# APA106_layout_test.net
KiCad netlist of a schematic drawn in EAGLE
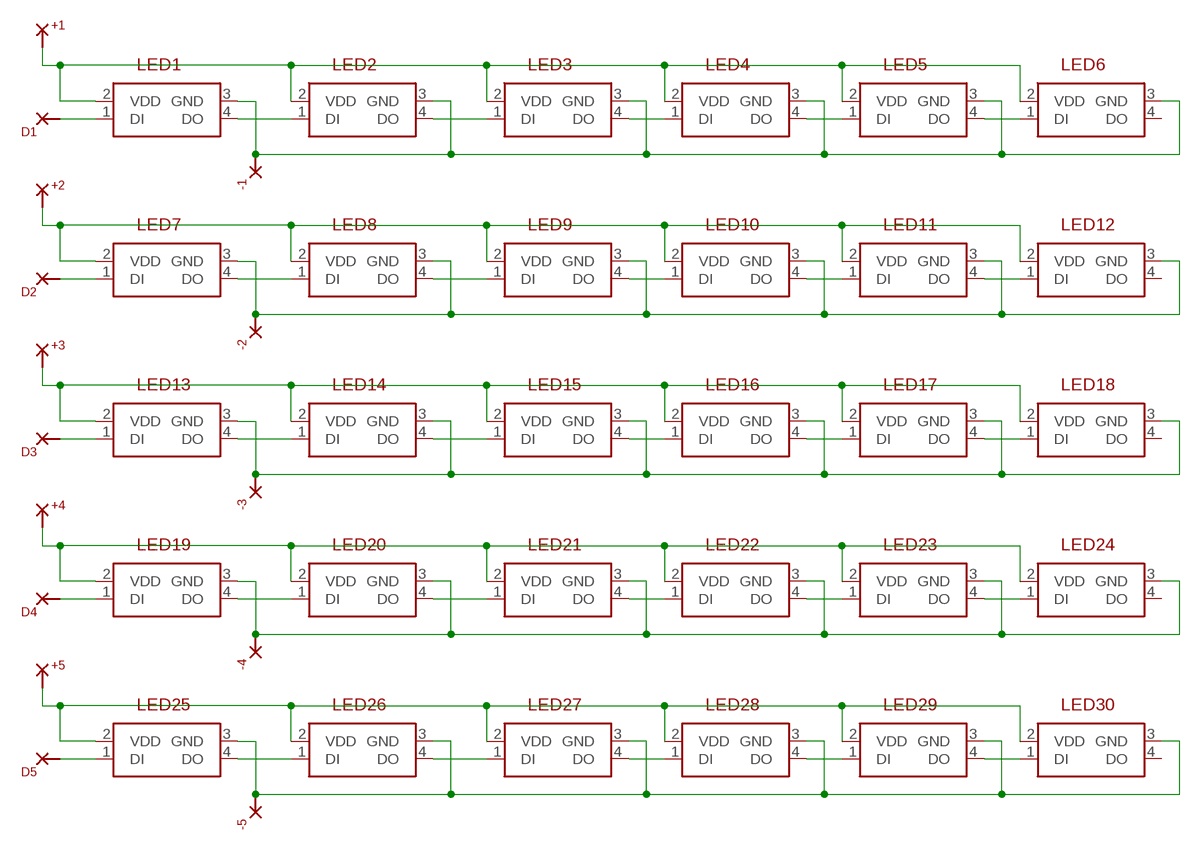
[diagram p0: schematic, sheet 1]

(export (version "E")
  (design (tool "Eeschema 10.0.6"))
  (components
    (comp (ref "+1")
      (value "WIRE-TEST-LOOP")
      (footprint "eagle-import:WIRE-TEST-LOOP")
      (libsource (lib "eagle-import") (part "WIRE-TEST-LOOP"))
    )
    (comp (ref "+2")
      (value "WIRE-TEST-LOOP")
      (footprint "eagle-import:WIRE-TEST-LOOP")
      (libsource (lib "eagle-import") (part "WIRE-TEST-LOOP"))
    )
    (comp (ref "+3")
      (value "WIRE-TEST-LOOP")
      (footprint "eagle-import:WIRE-TEST-LOOP")
      (libsource (lib "eagle-import") (part "WIRE-TEST-LOOP"))
    )
    (comp (ref "+4")
      (value "WIRE-TEST-LOOP")
      (footprint "eagle-import:WIRE-TEST-LOOP")
      (libsource (lib "eagle-import") (part "WIRE-TEST-LOOP"))
    )
    (comp (ref "+5")
      (value "WIRE-TEST-LOOP")
      (footprint "eagle-import:WIRE-TEST-LOOP")
      (libsource (lib "eagle-import") (part "WIRE-TEST-LOOP"))
    )
    (comp (ref "-1")
      (value "WIRE-TEST-LOOP")
      (footprint "eagle-import:WIRE-TEST-LOOP")
      (libsource (lib "eagle-import") (part "WIRE-TEST-LOOP"))
    )
    (comp (ref "-2")
      (value "WIRE-TEST-LOOP")
      (footprint "eagle-import:WIRE-TEST-LOOP")
      (libsource (lib "eagle-import") (part "WIRE-TEST-LOOP"))
    )
    (comp (ref "-3")
      (value "WIRE-TEST-LOOP")
      (footprint "eagle-import:WIRE-TEST-LOOP")
      (libsource (lib "eagle-import") (part "WIRE-TEST-LOOP"))
    )
    (comp (ref "-4")
      (value "WIRE-TEST-LOOP")
      (footprint "eagle-import:WIRE-TEST-LOOP")
      (libsource (lib "eagle-import") (part "WIRE-TEST-LOOP"))
    )
    (comp (ref "-5")
      (value "WIRE-TEST-LOOP")
      (footprint "eagle-import:WIRE-TEST-LOOP")
      (libsource (lib "eagle-import") (part "WIRE-TEST-LOOP"))
    )
    (comp (ref "D1")
      (value "WIRE-TEST-LOOP")
      (footprint "eagle-import:WIRE-TEST-LOOP")
      (libsource (lib "eagle-import") (part "WIRE-TEST-LOOP"))
    )
    (comp (ref "D2")
      (value "WIRE-TEST-LOOP")
      (footprint "eagle-import:WIRE-TEST-LOOP")
      (libsource (lib "eagle-import") (part "WIRE-TEST-LOOP"))
    )
    (comp (ref "D3")
      (value "WIRE-TEST-LOOP")
      (footprint "eagle-import:WIRE-TEST-LOOP")
      (libsource (lib "eagle-import") (part "WIRE-TEST-LOOP"))
    )
    (comp (ref "D4")
      (value "WIRE-TEST-LOOP")
      (footprint "eagle-import:WIRE-TEST-LOOP")
      (libsource (lib "eagle-import") (part "WIRE-TEST-LOOP"))
    )
    (comp (ref "D5")
      (value "WIRE-TEST-LOOP")
      (footprint "eagle-import:WIRE-TEST-LOOP")
      (libsource (lib "eagle-import") (part "WIRE-TEST-LOOP"))
    )
    (comp (ref "LED1")
      (value "LED-APA106HOLE-OFFSET-SPREAD")
      (footprint "eagle-import:LED-5MM-4PIN-HOLE-OFFSET-SPREAD")
      (libsource (lib "eagle-import") (part "LED-APA106HOLE-OFFSET-SPREAD"))
    )
    (comp (ref "LED2")
      (value "LED-APA106HOLE-OFFSET-SPREAD")
      (footprint "eagle-import:LED-5MM-4PIN-HOLE-OFFSET-SPREAD")
      (libsource (lib "eagle-import") (part "LED-APA106HOLE-OFFSET-SPREAD"))
    )
    (comp (ref "LED3")
      (value "LED-APA106HOLE-OFFSET-SPREAD")
      (footprint "eagle-import:LED-5MM-4PIN-HOLE-OFFSET-SPREAD")
      (libsource (lib "eagle-import") (part "LED-APA106HOLE-OFFSET-SPREAD"))
    )
    (comp (ref "LED4")
      (value "LED-APA106HOLE-OFFSET-SPREAD")
      (footprint "eagle-import:LED-5MM-4PIN-HOLE-OFFSET-SPREAD")
      (libsource (lib "eagle-import") (part "LED-APA106HOLE-OFFSET-SPREAD"))
    )
    (comp (ref "LED5")
      (value "LED-APA106HOLE-OFFSET-SPREAD")
      (footprint "eagle-import:LED-5MM-4PIN-HOLE-OFFSET-SPREAD")
      (libsource (lib "eagle-import") (part "LED-APA106HOLE-OFFSET-SPREAD"))
    )
    (comp (ref "LED6")
      (value "LED-APA106HOLE-OFFSET-SPREAD")
      (footprint "eagle-import:LED-5MM-4PIN-HOLE-OFFSET-SPREAD")
      (libsource (lib "eagle-import") (part "LED-APA106HOLE-OFFSET-SPREAD"))
    )
    (comp (ref "LED7")
      (value "LED-APA106SPREAD")
      (footprint "eagle-import:LED-5MM-4PIN-SPREAD")
      (libsource (lib "eagle-import") (part "LED-APA106SPREAD"))
    )
    (comp (ref "LED8")
      (value "LED-APA106SPREAD")
      (footprint "eagle-import:LED-5MM-4PIN-SPREAD")
      (libsource (lib "eagle-import") (part "LED-APA106SPREAD"))
    )
    (comp (ref "LED9")
      (value "LED-APA106SPREAD")
      (footprint "eagle-import:LED-5MM-4PIN-SPREAD")
      (libsource (lib "eagle-import") (part "LED-APA106SPREAD"))
    )
    (comp (ref "LED10")
      (value "LED-APA106SPREAD")
      (footprint "eagle-import:LED-5MM-4PIN-SPREAD")
      (libsource (lib "eagle-import") (part "LED-APA106SPREAD"))
    )
    (comp (ref "LED11")
      (value "LED-APA106SPREAD")
      (footprint "eagle-import:LED-5MM-4PIN-SPREAD")
      (libsource (lib "eagle-import") (part "LED-APA106SPREAD"))
    )
    (comp (ref "LED12")
      (value "LED-APA106SPREAD")
      (footprint "eagle-import:LED-5MM-4PIN-SPREAD")
      (libsource (lib "eagle-import") (part "LED-APA106SPREAD"))
    )
    (comp (ref "LED13")
      (value "LED-APA106OFFSET")
      (footprint "eagle-import:LED-5MM-4PIN-OFFSET")
      (libsource (lib "eagle-import") (part "LED-APA106OFFSET"))
    )
    (comp (ref "LED14")
      (value "LED-APA106OFFSET")
      (footprint "eagle-import:LED-5MM-4PIN-OFFSET")
      (libsource (lib "eagle-import") (part "LED-APA106OFFSET"))
    )
    (comp (ref "LED15")
      (value "LED-APA106OFFSET")
      (footprint "eagle-import:LED-5MM-4PIN-OFFSET")
      (libsource (lib "eagle-import") (part "LED-APA106OFFSET"))
    )
    (comp (ref "LED16")
      (value "LED-APA106OFFSET")
      (footprint "eagle-import:LED-5MM-4PIN-OFFSET")
      (libsource (lib "eagle-import") (part "LED-APA106OFFSET"))
    )
    (comp (ref "LED17")
      (value "LED-APA106OFFSET")
      (footprint "eagle-import:LED-5MM-4PIN-OFFSET")
      (libsource (lib "eagle-import") (part "LED-APA106OFFSET"))
    )
    (comp (ref "LED18")
      (value "LED-APA106OFFSET")
      (footprint "eagle-import:LED-5MM-4PIN-OFFSET")
      (libsource (lib "eagle-import") (part "LED-APA106OFFSET"))
    )
    (comp (ref "LED19")
      (value "LED-APA106SPREAD-OFFSET")
      (footprint "eagle-import:LED-5MM-4PIN-SPREAD-OFFSET")
      (libsource (lib "eagle-import") (part "LED-APA106SPREAD-OFFSET"))
    )
    (comp (ref "LED20")
      (value "LED-APA106SPREAD-OFFSET")
      (footprint "eagle-import:LED-5MM-4PIN-SPREAD-OFFSET")
      (libsource (lib "eagle-import") (part "LED-APA106SPREAD-OFFSET"))
    )
    (comp (ref "LED21")
      (value "LED-APA106SPREAD-OFFSET")
      (footprint "eagle-import:LED-5MM-4PIN-SPREAD-OFFSET")
      (libsource (lib "eagle-import") (part "LED-APA106SPREAD-OFFSET"))
    )
    (comp (ref "LED22")
      (value "LED-APA106SPREAD-OFFSET")
      (footprint "eagle-import:LED-5MM-4PIN-SPREAD-OFFSET")
      (libsource (lib "eagle-import") (part "LED-APA106SPREAD-OFFSET"))
    )
    (comp (ref "LED23")
      (value "LED-APA106SPREAD-OFFSET")
      (footprint "eagle-import:LED-5MM-4PIN-SPREAD-OFFSET")
      (libsource (lib "eagle-import") (part "LED-APA106SPREAD-OFFSET"))
    )
    (comp (ref "LED24")
      (value "LED-APA106SPREAD-OFFSET")
      (footprint "eagle-import:LED-5MM-4PIN-SPREAD-OFFSET")
      (libsource (lib "eagle-import") (part "LED-APA106SPREAD-OFFSET"))
    )
    (comp (ref "LED25")
      (value "LED-APA106HOLE-OFFSET")
      (footprint "eagle-import:LED-5MM-4PIN-HOLE-OFFSET")
      (libsource (lib "eagle-import") (part "LED-APA106HOLE-OFFSET"))
    )
    (comp (ref "LED26")
      (value "LED-APA106HOLE-OFFSET")
      (footprint "eagle-import:LED-5MM-4PIN-HOLE-OFFSET")
      (libsource (lib "eagle-import") (part "LED-APA106HOLE-OFFSET"))
    )
    (comp (ref "LED27")
      (value "LED-APA106HOLE-OFFSET")
      (footprint "eagle-import:LED-5MM-4PIN-HOLE-OFFSET")
      (libsource (lib "eagle-import") (part "LED-APA106HOLE-OFFSET"))
    )
    (comp (ref "LED28")
      (value "LED-APA106HOLE-OFFSET")
      (footprint "eagle-import:LED-5MM-4PIN-HOLE-OFFSET")
      (libsource (lib "eagle-import") (part "LED-APA106HOLE-OFFSET"))
    )
    (comp (ref "LED29")
      (value "LED-APA106HOLE-OFFSET")
      (footprint "eagle-import:LED-5MM-4PIN-HOLE-OFFSET")
      (libsource (lib "eagle-import") (part "LED-APA106HOLE-OFFSET"))
    )
    (comp (ref "LED30")
      (value "LED-APA106HOLE-OFFSET")
      (footprint "eagle-import:LED-5MM-4PIN-HOLE-OFFSET")
      (libsource (lib "eagle-import") (part "LED-APA106HOLE-OFFSET"))
    )
  )
  (nets
    (net (code "1") (name "Net-(LED1-DI)") (class "Default")
      (node (ref "D1") (pin "HOLE1") (pinfunction "1_HOLE1") (pintype "bidirectional"))
      (node (ref "D1") (pin "HOLE2") (pinfunction "1_HOLE2") (pintype "bidirectional"))
      (node (ref "D1") (pin "PAD") (pinfunction "1_PAD") (pintype "bidirectional"))
      (node (ref "LED1") (pin "1") (pinfunction "DI_1") (pintype "input"))
    )
    (net (code "2") (name "Net-(LED1-DO)") (class "Default")
      (node (ref "LED1") (pin "4") (pinfunction "DO_4") (pintype "output"))
      (node (ref "LED2") (pin "1") (pinfunction "DI_1") (pintype "input"))
    )
    (net (code "3") (name "Net-(LED1-GND)") (class "Default")
      (node (ref "-1") (pin "HOLE1") (pinfunction "1_HOLE1") (pintype "bidirectional"))
      (node (ref "-1") (pin "HOLE2") (pinfunction "1_HOLE2") (pintype "bidirectional"))
      (node (ref "-1") (pin "PAD") (pinfunction "1_PAD") (pintype "bidirectional"))
      (node (ref "LED1") (pin "3") (pinfunction "GND_3") (pintype "power_in"))
      (node (ref "LED2") (pin "3") (pinfunction "GND_3") (pintype "power_in"))
      (node (ref "LED3") (pin "3") (pinfunction "GND_3") (pintype "power_in"))
      (node (ref "LED4") (pin "3") (pinfunction "GND_3") (pintype "power_in"))
      (node (ref "LED5") (pin "3") (pinfunction "GND_3") (pintype "power_in"))
      (node (ref "LED6") (pin "3") (pinfunction "GND_3") (pintype "power_in"))
    )
    (net (code "4") (name "Net-(LED1-VDD)") (class "Default")
      (node (ref "+1") (pin "HOLE1") (pinfunction "1_HOLE1") (pintype "bidirectional"))
      (node (ref "+1") (pin "HOLE2") (pinfunction "1_HOLE2") (pintype "bidirectional"))
      (node (ref "+1") (pin "PAD") (pinfunction "1_PAD") (pintype "bidirectional"))
      (node (ref "LED1") (pin "2") (pinfunction "VDD_2") (pintype "power_in"))
      (node (ref "LED2") (pin "2") (pinfunction "VDD_2") (pintype "power_in"))
      (node (ref "LED3") (pin "2") (pinfunction "VDD_2") (pintype "power_in"))
      (node (ref "LED4") (pin "2") (pinfunction "VDD_2") (pintype "power_in"))
      (node (ref "LED5") (pin "2") (pinfunction "VDD_2") (pintype "power_in"))
      (node (ref "LED6") (pin "2") (pinfunction "VDD_2") (pintype "power_in"))
    )
    (net (code "5") (name "Net-(LED2-DO)") (class "Default")
      (node (ref "LED2") (pin "4") (pinfunction "DO_4") (pintype "output"))
      (node (ref "LED3") (pin "1") (pinfunction "DI_1") (pintype "input"))
    )
    (net (code "6") (name "Net-(LED3-DO)") (class "Default")
      (node (ref "LED3") (pin "4") (pinfunction "DO_4") (pintype "output"))
      (node (ref "LED4") (pin "1") (pinfunction "DI_1") (pintype "input"))
    )
    (net (code "7") (name "Net-(LED4-DO)") (class "Default")
      (node (ref "LED4") (pin "4") (pinfunction "DO_4") (pintype "output"))
      (node (ref "LED5") (pin "1") (pinfunction "DI_1") (pintype "input"))
    )
    (net (code "8") (name "Net-(LED5-DO)") (class "Default")
      (node (ref "LED5") (pin "4") (pinfunction "DO_4") (pintype "output"))
      (node (ref "LED6") (pin "1") (pinfunction "DI_1") (pintype "input"))
    )
    (net (code "9") (name "Net-(LED7-DI)") (class "Default")
      (node (ref "D2") (pin "HOLE1") (pinfunction "1_HOLE1") (pintype "bidirectional"))
      (node (ref "D2") (pin "HOLE2") (pinfunction "1_HOLE2") (pintype "bidirectional"))
      (node (ref "D2") (pin "PAD") (pinfunction "1_PAD") (pintype "bidirectional"))
      (node (ref "LED7") (pin "1") (pinfunction "DI_1") (pintype "input"))
    )
    (net (code "10") (name "Net-(LED7-DO)") (class "Default")
      (node (ref "LED7") (pin "4") (pinfunction "DO_4") (pintype "output"))
      (node (ref "LED8") (pin "1") (pinfunction "DI_1") (pintype "input"))
    )
    (net (code "11") (name "Net-(LED8-DO)") (class "Default")
      (node (ref "LED8") (pin "4") (pinfunction "DO_4") (pintype "output"))
      (node (ref "LED9") (pin "1") (pinfunction "DI_1") (pintype "input"))
    )
    (net (code "12") (name "Net-(LED10-DI)") (class "Default")
      (node (ref "LED10") (pin "1") (pinfunction "DI_1") (pintype "input"))
      (node (ref "LED9") (pin "4") (pinfunction "DO_4") (pintype "output"))
    )
    (net (code "13") (name "Net-(LED10-DO)") (class "Default")
      (node (ref "LED10") (pin "4") (pinfunction "DO_4") (pintype "output"))
      (node (ref "LED11") (pin "1") (pinfunction "DI_1") (pintype "input"))
    )
    (net (code "14") (name "Net-(LED10-GND)") (class "Default")
      (node (ref "-2") (pin "HOLE1") (pinfunction "1_HOLE1") (pintype "bidirectional"))
      (node (ref "-2") (pin "HOLE2") (pinfunction "1_HOLE2") (pintype "bidirectional"))
      (node (ref "-2") (pin "PAD") (pinfunction "1_PAD") (pintype "bidirectional"))
      (node (ref "LED10") (pin "3") (pinfunction "GND_3") (pintype "power_in"))
      (node (ref "LED11") (pin "3") (pinfunction "GND_3") (pintype "power_in"))
      (node (ref "LED12") (pin "3") (pinfunction "GND_3") (pintype "power_in"))
      (node (ref "LED7") (pin "3") (pinfunction "GND_3") (pintype "power_in"))
      (node (ref "LED8") (pin "3") (pinfunction "GND_3") (pintype "power_in"))
      (node (ref "LED9") (pin "3") (pinfunction "GND_3") (pintype "power_in"))
    )
    (net (code "15") (name "Net-(LED10-VDD)") (class "Default")
      (node (ref "+2") (pin "HOLE1") (pinfunction "1_HOLE1") (pintype "bidirectional"))
      (node (ref "+2") (pin "HOLE2") (pinfunction "1_HOLE2") (pintype "bidirectional"))
      (node (ref "+2") (pin "PAD") (pinfunction "1_PAD") (pintype "bidirectional"))
      (node (ref "LED10") (pin "2") (pinfunction "VDD_2") (pintype "power_in"))
      (node (ref "LED11") (pin "2") (pinfunction "VDD_2") (pintype "power_in"))
      (node (ref "LED12") (pin "2") (pinfunction "VDD_2") (pintype "power_in"))
      (node (ref "LED7") (pin "2") (pinfunction "VDD_2") (pintype "power_in"))
      (node (ref "LED8") (pin "2") (pinfunction "VDD_2") (pintype "power_in"))
      (node (ref "LED9") (pin "2") (pinfunction "VDD_2") (pintype "power_in"))
    )
    (net (code "16") (name "Net-(LED11-DO)") (class "Default")
      (node (ref "LED11") (pin "4") (pinfunction "DO_4") (pintype "output"))
      (node (ref "LED12") (pin "1") (pinfunction "DI_1") (pintype "input"))
    )
    (net (code "17") (name "Net-(LED13-DI)") (class "Default")
      (node (ref "D3") (pin "HOLE1") (pinfunction "1_HOLE1") (pintype "bidirectional"))
      (node (ref "D3") (pin "HOLE2") (pinfunction "1_HOLE2") (pintype "bidirectional"))
      (node (ref "D3") (pin "PAD") (pinfunction "1_PAD") (pintype "bidirectional"))
      (node (ref "LED13") (pin "1") (pinfunction "DI_1") (pintype "input"))
    )
    (net (code "18") (name "Net-(LED13-DO)") (class "Default")
      (node (ref "LED13") (pin "4") (pinfunction "DO_4") (pintype "output"))
      (node (ref "LED14") (pin "1") (pinfunction "DI_1") (pintype "input"))
    )
    (net (code "19") (name "Net-(LED13-GND)") (class "Default")
      (node (ref "-3") (pin "HOLE1") (pinfunction "1_HOLE1") (pintype "bidirectional"))
      (node (ref "-3") (pin "HOLE2") (pinfunction "1_HOLE2") (pintype "bidirectional"))
      (node (ref "-3") (pin "PAD") (pinfunction "1_PAD") (pintype "bidirectional"))
      (node (ref "LED13") (pin "3") (pinfunction "GND_3") (pintype "power_in"))
      (node (ref "LED14") (pin "3") (pinfunction "GND_3") (pintype "power_in"))
      (node (ref "LED15") (pin "3") (pinfunction "GND_3") (pintype "power_in"))
      (node (ref "LED16") (pin "3") (pinfunction "GND_3") (pintype "power_in"))
      (node (ref "LED17") (pin "3") (pinfunction "GND_3") (pintype "power_in"))
      (node (ref "LED18") (pin "3") (pinfunction "GND_3") (pintype "power_in"))
    )
    (net (code "20") (name "Net-(LED13-VDD)") (class "Default")
      (node (ref "+3") (pin "HOLE1") (pinfunction "1_HOLE1") (pintype "bidirectional"))
      (node (ref "+3") (pin "HOLE2") (pinfunction "1_HOLE2") (pintype "bidirectional"))
      (node (ref "+3") (pin "PAD") (pinfunction "1_PAD") (pintype "bidirectional"))
      (node (ref "LED13") (pin "2") (pinfunction "VDD_2") (pintype "power_in"))
      (node (ref "LED14") (pin "2") (pinfunction "VDD_2") (pintype "power_in"))
      (node (ref "LED15") (pin "2") (pinfunction "VDD_2") (pintype "power_in"))
      (node (ref "LED16") (pin "2") (pinfunction "VDD_2") (pintype "power_in"))
      (node (ref "LED17") (pin "2") (pinfunction "VDD_2") (pintype "power_in"))
      (node (ref "LED18") (pin "2") (pinfunction "VDD_2") (pintype "power_in"))
    )
    (net (code "21") (name "Net-(LED14-DO)") (class "Default")
      (node (ref "LED14") (pin "4") (pinfunction "DO_4") (pintype "output"))
      (node (ref "LED15") (pin "1") (pinfunction "DI_1") (pintype "input"))
    )
    (net (code "22") (name "Net-(LED15-DO)") (class "Default")
      (node (ref "LED15") (pin "4") (pinfunction "DO_4") (pintype "output"))
      (node (ref "LED16") (pin "1") (pinfunction "DI_1") (pintype "input"))
    )
    (net (code "23") (name "Net-(LED16-DO)") (class "Default")
      (node (ref "LED16") (pin "4") (pinfunction "DO_4") (pintype "output"))
      (node (ref "LED17") (pin "1") (pinfunction "DI_1") (pintype "input"))
    )
    (net (code "24") (name "Net-(LED17-DO)") (class "Default")
      (node (ref "LED17") (pin "4") (pinfunction "DO_4") (pintype "output"))
      (node (ref "LED18") (pin "1") (pinfunction "DI_1") (pintype "input"))
    )
    (net (code "25") (name "Net-(LED19-DI)") (class "Default")
      (node (ref "D4") (pin "HOLE1") (pinfunction "1_HOLE1") (pintype "bidirectional"))
      (node (ref "D4") (pin "HOLE2") (pinfunction "1_HOLE2") (pintype "bidirectional"))
      (node (ref "D4") (pin "PAD") (pinfunction "1_PAD") (pintype "bidirectional"))
      (node (ref "LED19") (pin "1") (pinfunction "DI_1") (pintype "input"))
    )
    (net (code "26") (name "Net-(LED19-DO)") (class "Default")
      (node (ref "LED19") (pin "4") (pinfunction "DO_4") (pintype "output"))
      (node (ref "LED20") (pin "1") (pinfunction "DI_1") (pintype "input"))
    )
    (net (code "27") (name "Net-(LED19-GND)") (class "Default")
      (node (ref "-4") (pin "HOLE1") (pinfunction "1_HOLE1") (pintype "bidirectional"))
      (node (ref "-4") (pin "HOLE2") (pinfunction "1_HOLE2") (pintype "bidirectional"))
      (node (ref "-4") (pin "PAD") (pinfunction "1_PAD") (pintype "bidirectional"))
      (node (ref "LED19") (pin "3") (pinfunction "GND_3") (pintype "power_in"))
      (node (ref "LED20") (pin "3") (pinfunction "GND_3") (pintype "power_in"))
      (node (ref "LED21") (pin "3") (pinfunction "GND_3") (pintype "power_in"))
      (node (ref "LED22") (pin "3") (pinfunction "GND_3") (pintype "power_in"))
      (node (ref "LED23") (pin "3") (pinfunction "GND_3") (pintype "power_in"))
      (node (ref "LED24") (pin "3") (pinfunction "GND_3") (pintype "power_in"))
    )
    (net (code "28") (name "Net-(LED19-VDD)") (class "Default")
      (node (ref "+4") (pin "HOLE1") (pinfunction "1_HOLE1") (pintype "bidirectional"))
      (node (ref "+4") (pin "HOLE2") (pinfunction "1_HOLE2") (pintype "bidirectional"))
      (node (ref "+4") (pin "PAD") (pinfunction "1_PAD") (pintype "bidirectional"))
      (node (ref "LED19") (pin "2") (pinfunction "VDD_2") (pintype "power_in"))
      (node (ref "LED20") (pin "2") (pinfunction "VDD_2") (pintype "power_in"))
      (node (ref "LED21") (pin "2") (pinfunction "VDD_2") (pintype "power_in"))
      (node (ref "LED22") (pin "2") (pinfunction "VDD_2") (pintype "power_in"))
      (node (ref "LED23") (pin "2") (pinfunction "VDD_2") (pintype "power_in"))
      (node (ref "LED24") (pin "2") (pinfunction "VDD_2") (pintype "power_in"))
    )
    (net (code "29") (name "Net-(LED20-DO)") (class "Default")
      (node (ref "LED20") (pin "4") (pinfunction "DO_4") (pintype "output"))
      (node (ref "LED21") (pin "1") (pinfunction "DI_1") (pintype "input"))
    )
    (net (code "30") (name "Net-(LED21-DO)") (class "Default")
      (node (ref "LED21") (pin "4") (pinfunction "DO_4") (pintype "output"))
      (node (ref "LED22") (pin "1") (pinfunction "DI_1") (pintype "input"))
    )
    (net (code "31") (name "Net-(LED22-DO)") (class "Default")
      (node (ref "LED22") (pin "4") (pinfunction "DO_4") (pintype "output"))
      (node (ref "LED23") (pin "1") (pinfunction "DI_1") (pintype "input"))
    )
    (net (code "32") (name "Net-(LED23-DO)") (class "Default")
      (node (ref "LED23") (pin "4") (pinfunction "DO_4") (pintype "output"))
      (node (ref "LED24") (pin "1") (pinfunction "DI_1") (pintype "input"))
    )
    (net (code "33") (name "Net-(LED25-DI)") (class "Default")
      (node (ref "D5") (pin "HOLE1") (pinfunction "1_HOLE1") (pintype "bidirectional"))
      (node (ref "D5") (pin "HOLE2") (pinfunction "1_HOLE2") (pintype "bidirectional"))
      (node (ref "D5") (pin "PAD") (pinfunction "1_PAD") (pintype "bidirectional"))
      (node (ref "LED25") (pin "1") (pinfunction "DI_1") (pintype "input"))
    )
    (net (code "34") (name "Net-(LED25-DO)") (class "Default")
      (node (ref "LED25") (pin "4") (pinfunction "DO_4") (pintype "output"))
      (node (ref "LED26") (pin "1") (pinfunction "DI_1") (pintype "input"))
    )
    (net (code "35") (name "Net-(LED25-GND)") (class "Default")
      (node (ref "-5") (pin "HOLE1") (pinfunction "1_HOLE1") (pintype "bidirectional"))
      (node (ref "-5") (pin "HOLE2") (pinfunction "1_HOLE2") (pintype "bidirectional"))
      (node (ref "-5") (pin "PAD") (pinfunction "1_PAD") (pintype "bidirectional"))
      (node (ref "LED25") (pin "3") (pinfunction "GND_3") (pintype "power_in"))
      (node (ref "LED26") (pin "3") (pinfunction "GND_3") (pintype "power_in"))
      (node (ref "LED27") (pin "3") (pinfunction "GND_3") (pintype "power_in"))
      (node (ref "LED28") (pin "3") (pinfunction "GND_3") (pintype "power_in"))
      (node (ref "LED29") (pin "3") (pinfunction "GND_3") (pintype "power_in"))
      (node (ref "LED30") (pin "3") (pinfunction "GND_3") (pintype "power_in"))
    )
    (net (code "36") (name "Net-(LED25-VDD)") (class "Default")
      (node (ref "+5") (pin "HOLE1") (pinfunction "1_HOLE1") (pintype "bidirectional"))
      (node (ref "+5") (pin "HOLE2") (pinfunction "1_HOLE2") (pintype "bidirectional"))
      (node (ref "+5") (pin "PAD") (pinfunction "1_PAD") (pintype "bidirectional"))
      (node (ref "LED25") (pin "2") (pinfunction "VDD_2") (pintype "power_in"))
      (node (ref "LED26") (pin "2") (pinfunction "VDD_2") (pintype "power_in"))
      (node (ref "LED27") (pin "2") (pinfunction "VDD_2") (pintype "power_in"))
      (node (ref "LED28") (pin "2") (pinfunction "VDD_2") (pintype "power_in"))
      (node (ref "LED29") (pin "2") (pinfunction "VDD_2") (pintype "power_in"))
      (node (ref "LED30") (pin "2") (pinfunction "VDD_2") (pintype "power_in"))
    )
    (net (code "37") (name "Net-(LED26-DO)") (class "Default")
      (node (ref "LED26") (pin "4") (pinfunction "DO_4") (pintype "output"))
      (node (ref "LED27") (pin "1") (pinfunction "DI_1") (pintype "input"))
    )
    (net (code "38") (name "Net-(LED27-DO)") (class "Default")
      (node (ref "LED27") (pin "4") (pinfunction "DO_4") (pintype "output"))
      (node (ref "LED28") (pin "1") (pinfunction "DI_1") (pintype "input"))
    )
    (net (code "39") (name "Net-(LED28-DO)") (class "Default")
      (node (ref "LED28") (pin "4") (pinfunction "DO_4") (pintype "output"))
      (node (ref "LED29") (pin "1") (pinfunction "DI_1") (pintype "input"))
    )
    (net (code "40") (name "Net-(LED29-DO)") (class "Default")
      (node (ref "LED29") (pin "4") (pinfunction "DO_4") (pintype "output"))
      (node (ref "LED30") (pin "1") (pinfunction "DI_1") (pintype "input"))
    )
    (net (code "41") (name "unconnected-(LED6-DO-Pad4)") (class "Default")
      (node (ref "LED6") (pin "4") (pinfunction "DO_4") (pintype "output"))
    )
    (net (code "42") (name "unconnected-(LED12-DO-Pad4)") (class "Default")
      (node (ref "LED12") (pin "4") (pinfunction "DO_4") (pintype "output"))
    )
    (net (code "43") (name "unconnected-(LED18-DO-Pad4)") (class "Default")
      (node (ref "LED18") (pin "4") (pinfunction "DO_4") (pintype "output"))
    )
    (net (code "44") (name "unconnected-(LED24-DO-Pad4)") (class "Default")
      (node (ref "LED24") (pin "4") (pinfunction "DO_4") (pintype "output"))
    )
    (net (code "45") (name "unconnected-(LED30-DO-Pad4)") (class "Default")
      (node (ref "LED30") (pin "4") (pinfunction "DO_4") (pintype "output"))
    )
  )
)
